# Motherboard_v2.net
KiCad netlist of a schematic drawn in EAGLE
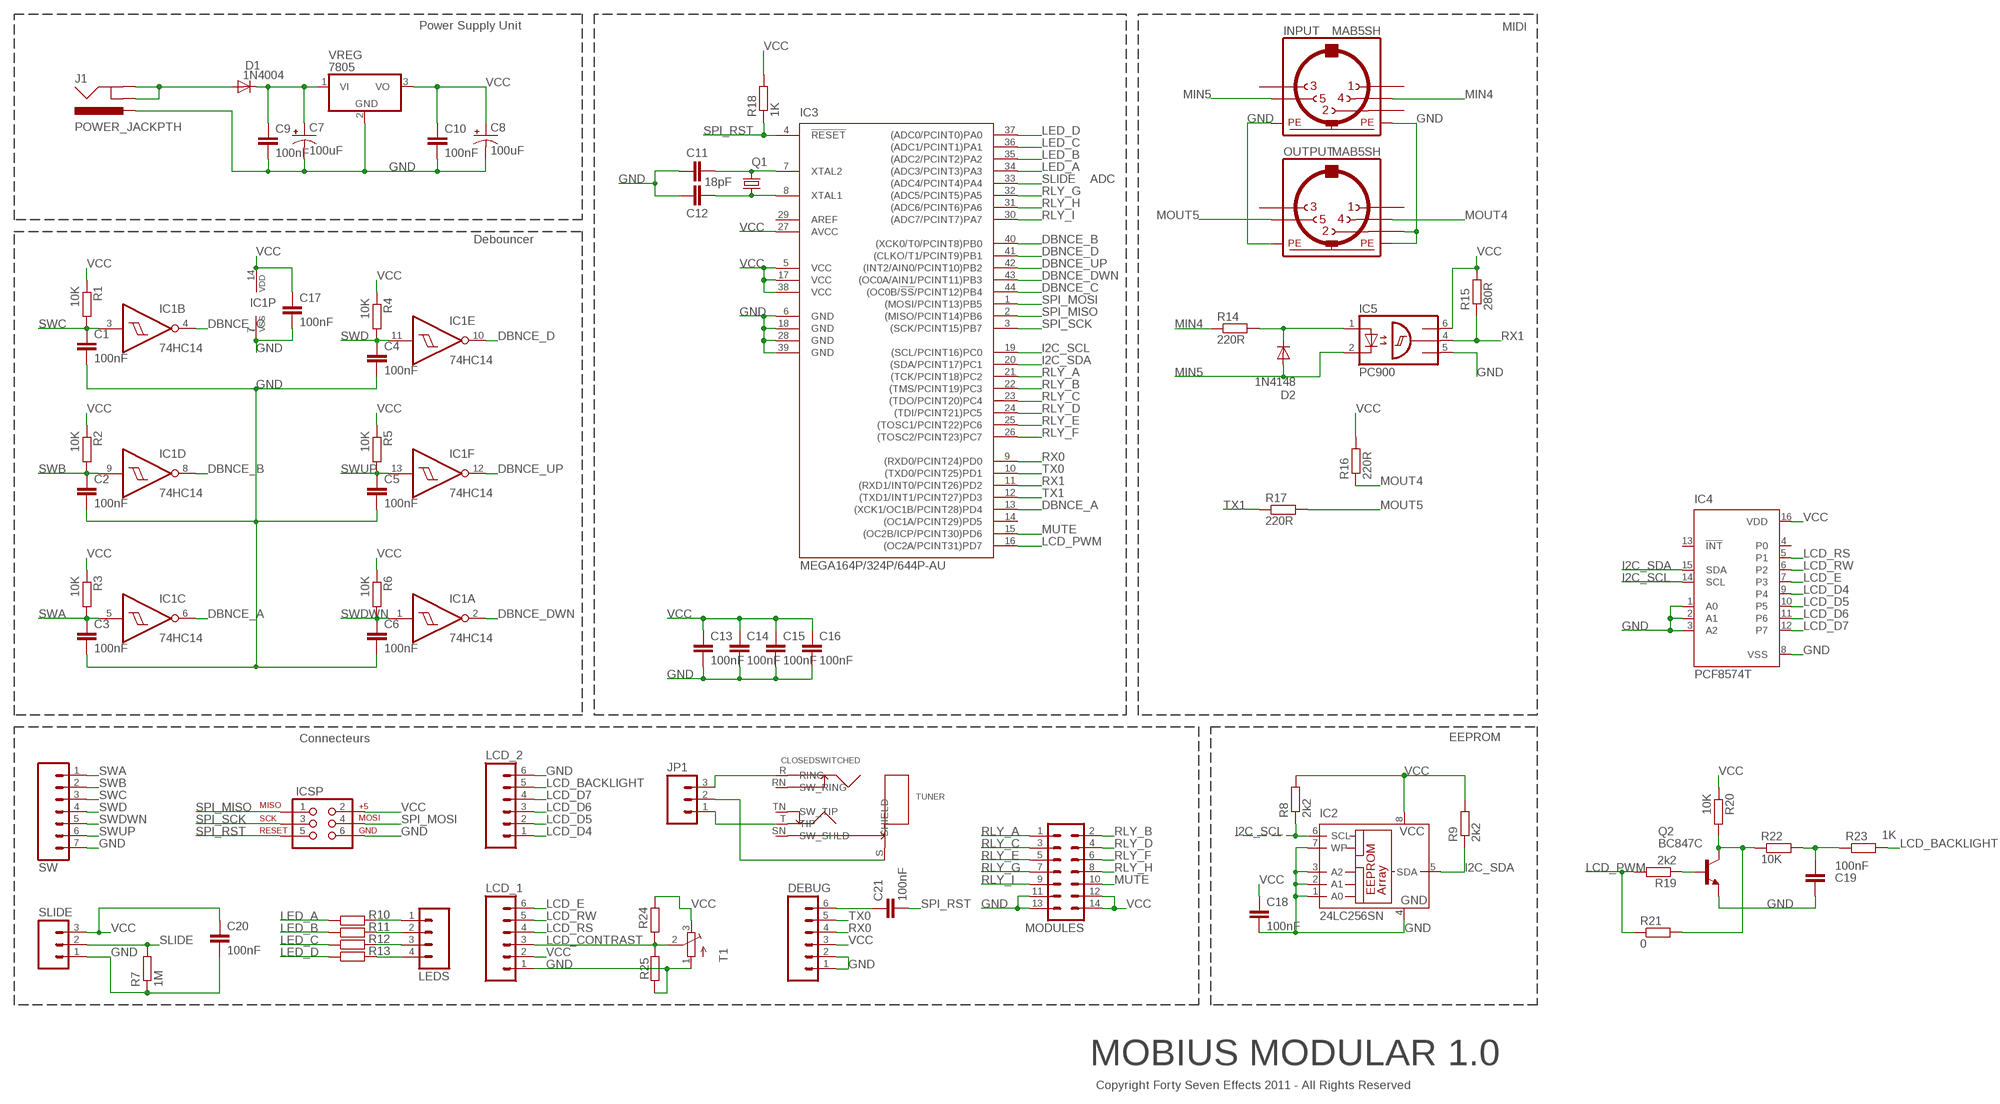
[diagram p0: schematic, sheet 1]

(export (version "E")
  (design (tool "Eeschema 10.0.6"))
  (components
    (comp (ref "C1")
      (value "100nF")
      (footprint "eagle-import:C0805K")
      (libsource (lib "eagle-import") (part "C-EUC0805K"))
    )
    (comp (ref "C2")
      (value "100nF")
      (footprint "eagle-import:C0805K")
      (libsource (lib "eagle-import") (part "C-EUC0805K"))
    )
    (comp (ref "C3")
      (value "100nF")
      (footprint "eagle-import:C0805K")
      (libsource (lib "eagle-import") (part "C-EUC0805K"))
    )
    (comp (ref "C4")
      (value "100nF")
      (footprint "eagle-import:C0805K")
      (libsource (lib "eagle-import") (part "C-EUC0805K"))
    )
    (comp (ref "C5")
      (value "100nF")
      (footprint "eagle-import:C0805K")
      (libsource (lib "eagle-import") (part "C-EUC0805K"))
    )
    (comp (ref "C6")
      (value "100nF")
      (footprint "eagle-import:C0805K")
      (libsource (lib "eagle-import") (part "C-EUC0805K"))
    )
    (comp (ref "C7")
      (value "100uF")
      (footprint "eagle-import:E2,5-6E")
      (libsource (lib "eagle-import") (part "CPOL-USE2,5-6E"))
    )
    (comp (ref "C8")
      (value "100uF")
      (footprint "eagle-import:E2,5-6E")
      (libsource (lib "eagle-import") (part "CPOL-USE2,5-6E"))
    )
    (comp (ref "C9")
      (value "100nF")
      (footprint "eagle-import:C0805K")
      (libsource (lib "eagle-import") (part "C-EUC0805K"))
    )
    (comp (ref "C10")
      (value "100nF")
      (footprint "eagle-import:C0805K")
      (libsource (lib "eagle-import") (part "C-EUC0805K"))
    )
    (comp (ref "C11")
      (value "18pF")
      (footprint "eagle-import:C0805K")
      (libsource (lib "eagle-import") (part "C-EUC0805K"))
    )
    (comp (ref "C12")
      (value "18pF")
      (footprint "eagle-import:C0805K")
      (libsource (lib "eagle-import") (part "C-EUC0805K"))
    )
    (comp (ref "C13")
      (value "100nF")
      (footprint "eagle-import:C0805K")
      (libsource (lib "eagle-import") (part "C-EUC0805K"))
    )
    (comp (ref "C14")
      (value "100nF")
      (footprint "eagle-import:C0805K")
      (libsource (lib "eagle-import") (part "C-EUC0805K"))
    )
    (comp (ref "C15")
      (value "100nF")
      (footprint "eagle-import:C0805K")
      (libsource (lib "eagle-import") (part "C-EUC0805K"))
    )
    (comp (ref "C16")
      (value "100nF")
      (footprint "eagle-import:C0805K")
      (libsource (lib "eagle-import") (part "C-EUC0805K"))
    )
    (comp (ref "C17")
      (value "100nF")
      (footprint "eagle-import:C0805K")
      (libsource (lib "eagle-import") (part "C-EUC0805K"))
    )
    (comp (ref "C18")
      (value "100nF")
      (footprint "eagle-import:C0805K")
      (libsource (lib "eagle-import") (part "C-EUC0805K"))
    )
    (comp (ref "C19")
      (value "100nF")
      (footprint "eagle-import:C0805K")
      (libsource (lib "eagle-import") (part "C-EUC0805K"))
    )
    (comp (ref "C20")
      (value "100nF")
      (footprint "eagle-import:C0805K")
      (libsource (lib "eagle-import") (part "C-EUC0805K"))
    )
    (comp (ref "C21")
      (value "100nF")
      (footprint "eagle-import:C0805K")
      (libsource (lib "eagle-import") (part "C-EUC0805K"))
    )
    (comp (ref "D1")
      (value "1N4004")
      (footprint "eagle-import:DO41-10")
      (libsource (lib "eagle-import") (part "1N4004"))
    )
    (comp (ref "D2")
      (value "1N4148")
      (footprint "eagle-import:DO35-7")
      (libsource (lib "eagle-import") (part "1N4148DO35-7"))
    )
    (comp (ref "DEBUG")
      (value "M06SIP")
      (footprint "eagle-import:1X06")
      (libsource (lib "eagle-import") (part "M06SIP"))
    )
    (comp (ref "IC1")
      (value "74HC14")
      (footprint "eagle-import:SO14")
      (libsource (lib "eagle-import") (part "40106D"))
    )
    (comp (ref "IC2")
      (value "24LC256SN")
      (footprint "eagle-import:SO-08")
      (libsource (lib "eagle-import") (part "24SNLC256"))
    )
    (comp (ref "IC3")
      (value "MEGA164P/324P/644P-AU")
      (footprint "eagle-import:TQFP44")
      (libsource (lib "eagle-import") (part "MEGA164P/324P/644P-AU"))
    )
    (comp (ref "IC4")
      (value "PCF8574T")
      (footprint "eagle-import:SO16W")
      (fields (field (name "MPN") "PCF8574T/3,512"))
      (libsource (lib "eagle-import") (part "PCF8574T"))
    )
    (comp (ref "IC5")
      (value "PC900")
      (footprint "eagle-import:DIL06")
      (libsource (lib "eagle-import") (part "OPI8013"))
    )
    (comp (ref "ICSP")
      (value "AVR_SPI_PRG_6PTH")
      (footprint "eagle-import:2X3")
      (libsource (lib "eagle-import") (part "AVR_SPI_PRG_6PTH"))
    )
    (comp (ref "INPUT")
      (value "MAB5SH")
      (footprint "eagle-import:MAB5SH")
      (libsource (lib "eagle-import") (part "MAB5SH"))
    )
    (comp (ref "J1")
      (value "POWER_JACKPTH")
      (footprint "eagle-import:POWER_JACK_PTH")
      (libsource (lib "eagle-import") (part "POWER_JACKPTH"))
    )
    (comp (ref "JP1")
      (value "M03POLAR")
      (footprint "eagle-import:MOLEX-1X3")
      (libsource (lib "eagle-import") (part "M03POLAR"))
    )
    (comp (ref "LCD_1")
      (value "M06SIP")
      (footprint "eagle-import:1X06")
      (libsource (lib "eagle-import") (part "M06SIP"))
    )
    (comp (ref "LCD_2")
      (value "M06SIP")
      (footprint "eagle-import:1X06")
      (libsource (lib "eagle-import") (part "M06SIP"))
    )
    (comp (ref "LEDS")
      (value "M04PTH")
      (footprint "eagle-import:1X04")
      (libsource (lib "eagle-import") (part "M04PTH"))
    )
    (comp (ref "MODULES")
      (value "ML14")
      (footprint "eagle-import:ML14")
      (libsource (lib "eagle-import") (part "ML14"))
    )
    (comp (ref "OUTPUT")
      (value "MAB5SH")
      (footprint "eagle-import:MAB5SH")
      (libsource (lib "eagle-import") (part "MAB5SH"))
    )
    (comp (ref "Q1")
      (value "16MHz")
      (footprint "eagle-import:CRYSTAL-SMD-5X3")
      (libsource (lib "eagle-import") (part "CRYSTAL5X3"))
    )
    (comp (ref "Q2")
      (value "BC847C")
      (footprint "eagle-import:SOT23")
      (libsource (lib "eagle-import") (part "BC847SMDC"))
    )
    (comp (ref "R1")
      (value "10K")
      (footprint "eagle-import:M0805")
      (libsource (lib "eagle-import") (part "R-EU_M0805"))
    )
    (comp (ref "R2")
      (value "10K")
      (footprint "eagle-import:M0805")
      (libsource (lib "eagle-import") (part "R-EU_M0805"))
    )
    (comp (ref "R3")
      (value "10K")
      (footprint "eagle-import:M0805")
      (libsource (lib "eagle-import") (part "R-EU_M0805"))
    )
    (comp (ref "R4")
      (value "10K")
      (footprint "eagle-import:M0805")
      (libsource (lib "eagle-import") (part "R-EU_M0805"))
    )
    (comp (ref "R5")
      (value "10K")
      (footprint "eagle-import:M0805")
      (libsource (lib "eagle-import") (part "R-EU_M0805"))
    )
    (comp (ref "R6")
      (value "10K")
      (footprint "eagle-import:M0805")
      (libsource (lib "eagle-import") (part "R-EU_M0805"))
    )
    (comp (ref "R7")
      (value "1M")
      (footprint "eagle-import:M0805")
      (libsource (lib "eagle-import") (part "R-EU_M0805"))
    )
    (comp (ref "R8")
      (value "2k2")
      (footprint "eagle-import:M0805")
      (libsource (lib "eagle-import") (part "R-EU_M0805"))
    )
    (comp (ref "R9")
      (value "2k2")
      (footprint "eagle-import:M0805")
      (libsource (lib "eagle-import") (part "R-EU_M0805"))
    )
    (comp (ref "R10")
      (value "1k")
      (footprint "eagle-import:M0805")
      (libsource (lib "eagle-import") (part "R-EU_M0805"))
    )
    (comp (ref "R11")
      (value "1K")
      (footprint "eagle-import:M0805")
      (libsource (lib "eagle-import") (part "R-EU_M0805"))
    )
    (comp (ref "R12")
      (value "1k")
      (footprint "eagle-import:M0805")
      (libsource (lib "eagle-import") (part "R-EU_M0805"))
    )
    (comp (ref "R13")
      (value "1k")
      (footprint "eagle-import:M0805")
      (libsource (lib "eagle-import") (part "R-EU_M0805"))
    )
    (comp (ref "R14")
      (value "220R")
      (footprint "eagle-import:M0805")
      (libsource (lib "eagle-import") (part "R-EU_M0805"))
    )
    (comp (ref "R15")
      (value "280R")
      (footprint "eagle-import:M0805")
      (libsource (lib "eagle-import") (part "R-EU_M0805"))
    )
    (comp (ref "R16")
      (value "220R")
      (footprint "eagle-import:M0805")
      (libsource (lib "eagle-import") (part "R-EU_M0805"))
    )
    (comp (ref "R17")
      (value "220R")
      (footprint "eagle-import:M0805")
      (libsource (lib "eagle-import") (part "R-EU_M0805"))
    )
    (comp (ref "R18")
      (value "1K")
      (footprint "eagle-import:M0805")
      (libsource (lib "eagle-import") (part "R-EU_M0805"))
    )
    (comp (ref "R19")
      (value "2k2")
      (footprint "eagle-import:M0805")
      (libsource (lib "eagle-import") (part "R-EU_M0805"))
    )
    (comp (ref "R20")
      (value "10K")
      (footprint "eagle-import:M0805")
      (libsource (lib "eagle-import") (part "R-EU_M0805"))
    )
    (comp (ref "R21")
      (value "0")
      (footprint "eagle-import:M0805")
      (libsource (lib "eagle-import") (part "R-EU_M0805"))
    )
    (comp (ref "R22")
      (value "10K")
      (footprint "eagle-import:M0805")
      (libsource (lib "eagle-import") (part "R-EU_M0805"))
    )
    (comp (ref "R23")
      (value "1K")
      (footprint "eagle-import:M0805")
      (libsource (lib "eagle-import") (part "R-EU_M0805"))
    )
    (comp (ref "R24")
      (value "1k")
      (footprint "eagle-import:M0805")
      (libsource (lib "eagle-import") (part "R-EU_M0805"))
    )
    (comp (ref "R25")
      (value "1k")
      (footprint "eagle-import:M0805")
      (libsource (lib "eagle-import") (part "R-EU_M0805"))
    )
    (comp (ref "SLIDE")
      (value "M03PTH")
      (footprint "eagle-import:1X03")
      (libsource (lib "eagle-import") (part "M03PTH"))
    )
    (comp (ref "SW")
      (value "M07")
      (footprint "eagle-import:1X07")
      (libsource (lib "eagle-import") (part "M07"))
    )
    (comp (ref "T1")
      (value "TRIMPOTTC33X")
      (footprint "eagle-import:TC33X")
      (libsource (lib "eagle-import") (part "TRIMPOTTC33X"))
    )
    (comp (ref "TUNER")
      (value "CLOSEDSWITCHED")
      (footprint "eagle-import:NMJ6HFD2")
      (libsource (lib "eagle-import") (part "CLOSEDSWITCHED"))
    )
    (comp (ref "VREG")
      (value "7805")
      (footprint "eagle-import:TO220V")
      (libsource (lib "eagle-import") (part "78TV05"))
    )
  )
  (nets
    (net (code "1") (name "/AREF") (class "Default")
      (node (ref "IC3") (pin "29") (pinfunction "AREF_29") (pintype "power_in"))
    )
    (net (code "2") (name "/DBNCE_A") (class "Default")
      (node (ref "IC1") (pin "6") (pinfunction "O_6") (pintype "output"))
      (node (ref "IC3") (pin "13") (pinfunction "(XCK1/OC1B/PCINT28)PD4_13") (pintype "bidirectional"))
    )
    (net (code "3") (name "/DBNCE_B") (class "Default")
      (node (ref "IC1") (pin "8") (pinfunction "O_8") (pintype "output"))
      (node (ref "IC3") (pin "40") (pinfunction "(XCK0/T0/PCINT8)PB0_40") (pintype "bidirectional"))
    )
    (net (code "4") (name "/DBNCE_C") (class "Default")
      (node (ref "IC1") (pin "4") (pinfunction "O_4") (pintype "output"))
      (node (ref "IC3") (pin "44") (pinfunction "(OC0B/~{SS}/PCINT12)PB4_44") (pintype "bidirectional"))
    )
    (net (code "5") (name "/DBNCE_D") (class "Default")
      (node (ref "IC1") (pin "10") (pinfunction "O_10") (pintype "output"))
      (node (ref "IC3") (pin "41") (pinfunction "(CLKO/T1/PCINT9)PB1_41") (pintype "bidirectional"))
    )
    (net (code "6") (name "/DBNCE_DWN") (class "Default")
      (node (ref "IC1") (pin "2") (pinfunction "O_2") (pintype "output"))
      (node (ref "IC3") (pin "43") (pinfunction "(OC0A/AIN1/PCINT11)PB3_43") (pintype "bidirectional"))
    )
    (net (code "7") (name "/DBNCE_UP") (class "Default")
      (node (ref "IC1") (pin "12") (pinfunction "O_12") (pintype "output"))
      (node (ref "IC3") (pin "42") (pinfunction "(INT2/AIN0/PCINT10)PB2_42") (pintype "bidirectional"))
    )
    (net (code "8") (name "/GND") (class "Default")
      (node (ref "C1") (pin "2") (pinfunction "2_2") (pintype "passive"))
      (node (ref "C10") (pin "2") (pinfunction "2_2") (pintype "passive"))
      (node (ref "C11") (pin "1") (pinfunction "1_1") (pintype "passive"))
      (node (ref "C12") (pin "1") (pinfunction "1_1") (pintype "passive"))
      (node (ref "C13") (pin "2") (pinfunction "2_2") (pintype "passive"))
      (node (ref "C14") (pin "2") (pinfunction "2_2") (pintype "passive"))
      (node (ref "C15") (pin "2") (pinfunction "2_2") (pintype "passive"))
      (node (ref "C16") (pin "2") (pinfunction "2_2") (pintype "passive"))
      (node (ref "C17") (pin "2") (pinfunction "2_2") (pintype "passive"))
      (node (ref "C18") (pin "2") (pinfunction "2_2") (pintype "passive"))
      (node (ref "C19") (pin "1") (pinfunction "1_1") (pintype "passive"))
      (node (ref "C2") (pin "2") (pinfunction "2_2") (pintype "passive"))
      (node (ref "C20") (pin "2") (pinfunction "2_2") (pintype "passive"))
      (node (ref "C3") (pin "2") (pinfunction "2_2") (pintype "passive"))
      (node (ref "C4") (pin "2") (pinfunction "2_2") (pintype "passive"))
      (node (ref "C5") (pin "2") (pinfunction "2_2") (pintype "passive"))
      (node (ref "C6") (pin "2") (pinfunction "2_2") (pintype "passive"))
      (node (ref "C7") (pin "-") (pinfunction "-_-") (pintype "passive"))
      (node (ref "C8") (pin "-") (pinfunction "-_-") (pintype "passive"))
      (node (ref "C9") (pin "2") (pinfunction "2_2") (pintype "passive"))
      (node (ref "DEBUG") (pin "1") (pinfunction "1_1") (pintype "passive"))
      (node (ref "DEBUG") (pin "2") (pinfunction "2_2") (pintype "passive"))
      (node (ref "IC1") (pin "7") (pinfunction "VSS_7") (pintype "power_in"))
      (node (ref "IC2") (pin "1") (pinfunction "A0_1") (pintype "input"))
      (node (ref "IC2") (pin "2") (pinfunction "A1_2") (pintype "input"))
      (node (ref "IC2") (pin "3") (pinfunction "A2_3") (pintype "input"))
      (node (ref "IC2") (pin "4") (pinfunction "GND_4") (pintype "power_in"))
      (node (ref "IC2") (pin "7") (pinfunction "WP_7") (pintype "input"))
      (node (ref "IC3") (pin "18") (pinfunction "GND_18") (pintype "power_in"))
      (node (ref "IC3") (pin "28") (pinfunction "GND_28") (pintype "power_in"))
      (node (ref "IC3") (pin "39") (pinfunction "GND_39") (pintype "power_in"))
      (node (ref "IC3") (pin "6") (pinfunction "GND_6") (pintype "power_in"))
      (node (ref "IC4") (pin "1") (pinfunction "A0_1") (pintype "input"))
      (node (ref "IC4") (pin "2") (pinfunction "A1_2") (pintype "input"))
      (node (ref "IC4") (pin "3") (pinfunction "A2_3") (pintype "input"))
      (node (ref "IC4") (pin "8") (pinfunction "VSS_8") (pintype "power_in"))
      (node (ref "IC5") (pin "5") (pinfunction "GND_5") (pintype "passive"))
      (node (ref "ICSP") (pin "6") (pinfunction "6_6") (pintype "passive"))
      (node (ref "INPUT") (pin "PE") (pinfunction "PE_PE") (pintype "power_in"))
      (node (ref "INPUT") (pin "PE@") (pinfunction "PE_PE@") (pintype "power_in"))
      (node (ref "J1") (pin "PWR") (pinfunction "PWR_PWR") (pintype "bidirectional"))
      (node (ref "LCD_1") (pin "1") (pinfunction "1_1") (pintype "passive"))
      (node (ref "LCD_2") (pin "6") (pinfunction "6_6") (pintype "passive"))
      (node (ref "MODULES") (pin "11") (pinfunction "11_11") (pintype "passive"))
      (node (ref "MODULES") (pin "13") (pinfunction "13_13") (pintype "passive"))
      (node (ref "OUTPUT") (pin "2") (pinfunction "2_2") (pintype "passive"))
      (node (ref "OUTPUT") (pin "PE") (pinfunction "PE_PE") (pintype "power_in"))
      (node (ref "OUTPUT") (pin "PE@") (pinfunction "PE_PE@") (pintype "power_in"))
      (node (ref "Q2") (pin "2") (pinfunction "E_2") (pintype "passive"))
      (node (ref "R25") (pin "1") (pinfunction "1_1") (pintype "passive"))
      (node (ref "R7") (pin "1") (pinfunction "1_1") (pintype "passive"))
      (node (ref "SLIDE") (pin "1") (pinfunction "1_1") (pintype "passive"))
      (node (ref "SW") (pin "7") (pinfunction "7_7") (pintype "passive"))
      (node (ref "T1") (pin "1") (pinfunction "A_1") (pintype "passive"))
      (node (ref "VREG") (pin "2") (pinfunction "GND_2") (pintype "passive"))
    )
    (net (code "9") (name "/I2C_SCL") (class "Default")
      (node (ref "IC2") (pin "6") (pinfunction "SCL_6") (pintype "input"))
      (node (ref "IC3") (pin "19") (pinfunction "(SCL/PCINT16)PC0_19") (pintype "bidirectional"))
      (node (ref "IC4") (pin "14") (pinfunction "SCL_14") (pintype "input"))
      (node (ref "R8") (pin "1") (pinfunction "1_1") (pintype "passive"))
    )
    (net (code "10") (name "/I2C_SDA") (class "Default")
      (node (ref "IC2") (pin "5") (pinfunction "SDA_5") (pintype "bidirectional"))
      (node (ref "IC3") (pin "20") (pinfunction "(SDA/PCINT17)PC1_20") (pintype "bidirectional"))
      (node (ref "IC4") (pin "15") (pinfunction "SDA_15") (pintype "bidirectional"))
      (node (ref "R9") (pin "1") (pinfunction "1_1") (pintype "passive"))
    )
    (net (code "11") (name "/LCD_BACKLIGHT") (class "Default")
      (node (ref "LCD_2") (pin "5") (pinfunction "5_5") (pintype "passive"))
      (node (ref "R23") (pin "2") (pinfunction "2_2") (pintype "passive"))
    )
    (net (code "12") (name "/LCD_CONTRAST") (class "Default")
      (node (ref "LCD_1") (pin "3") (pinfunction "3_3") (pintype "passive"))
      (node (ref "R24") (pin "1") (pinfunction "1_1") (pintype "passive"))
      (node (ref "R25") (pin "2") (pinfunction "2_2") (pintype "passive"))
      (node (ref "T1") (pin "2") (pinfunction "S_2") (pintype "passive"))
    )
    (net (code "13") (name "/LCD_D4") (class "Default")
      (node (ref "IC4") (pin "9") (pinfunction "P4_9") (pintype "bidirectional"))
      (node (ref "LCD_2") (pin "1") (pinfunction "1_1") (pintype "passive"))
    )
    (net (code "14") (name "/LCD_D5") (class "Default")
      (node (ref "IC4") (pin "10") (pinfunction "P5_10") (pintype "bidirectional"))
      (node (ref "LCD_2") (pin "2") (pinfunction "2_2") (pintype "passive"))
    )
    (net (code "15") (name "/LCD_D6") (class "Default")
      (node (ref "IC4") (pin "11") (pinfunction "P6_11") (pintype "bidirectional"))
      (node (ref "LCD_2") (pin "3") (pinfunction "3_3") (pintype "passive"))
    )
    (net (code "16") (name "/LCD_D7") (class "Default")
      (node (ref "IC4") (pin "12") (pinfunction "P7_12") (pintype "bidirectional"))
      (node (ref "LCD_2") (pin "4") (pinfunction "4_4") (pintype "passive"))
    )
    (net (code "17") (name "/LCD_E") (class "Default")
      (node (ref "IC4") (pin "7") (pinfunction "P3_7") (pintype "bidirectional"))
      (node (ref "LCD_1") (pin "6") (pinfunction "6_6") (pintype "passive"))
    )
    (net (code "18") (name "/LCD_PWM") (class "Default")
      (node (ref "IC3") (pin "16") (pinfunction "(OC2A/PCINT31)PD7_16") (pintype "bidirectional"))
      (node (ref "R19") (pin "2") (pinfunction "2_2") (pintype "passive"))
      (node (ref "R21") (pin "1") (pinfunction "1_1") (pintype "passive"))
    )
    (net (code "19") (name "/LCD_RS") (class "Default")
      (node (ref "IC4") (pin "5") (pinfunction "P1_5") (pintype "bidirectional"))
      (node (ref "LCD_1") (pin "4") (pinfunction "4_4") (pintype "passive"))
    )
    (net (code "20") (name "/LCD_RW") (class "Default")
      (node (ref "IC4") (pin "6") (pinfunction "P2_6") (pintype "bidirectional"))
      (node (ref "LCD_1") (pin "5") (pinfunction "5_5") (pintype "passive"))
    )
    (net (code "21") (name "/LED_A") (class "Default")
      (node (ref "IC3") (pin "34") (pinfunction "(ADC3/PCINT3)PA3_34") (pintype "bidirectional"))
      (node (ref "R10") (pin "1") (pinfunction "1_1") (pintype "passive"))
    )
    (net (code "22") (name "/LED_B") (class "Default")
      (node (ref "IC3") (pin "35") (pinfunction "(ADC2/PCINT2)PA2_35") (pintype "bidirectional"))
      (node (ref "R11") (pin "1") (pinfunction "1_1") (pintype "passive"))
    )
    (net (code "23") (name "/LED_C") (class "Default")
      (node (ref "IC3") (pin "36") (pinfunction "(ADC1/PCINT1)PA1_36") (pintype "bidirectional"))
      (node (ref "R12") (pin "1") (pinfunction "1_1") (pintype "passive"))
    )
    (net (code "24") (name "/LED_D") (class "Default")
      (node (ref "IC3") (pin "37") (pinfunction "(ADC0/PCINT0)PA0_37") (pintype "bidirectional"))
      (node (ref "R13") (pin "1") (pinfunction "1_1") (pintype "passive"))
    )
    (net (code "25") (name "/MIN4") (class "Default")
      (node (ref "INPUT") (pin "4") (pinfunction "4_4") (pintype "passive"))
      (node (ref "R14") (pin "1") (pinfunction "1_1") (pintype "passive"))
    )
    (net (code "26") (name "/MIN5") (class "Default")
      (node (ref "D2") (pin "A") (pinfunction "A_A") (pintype "passive"))
      (node (ref "IC5") (pin "2") (pinfunction "C_2") (pintype "passive"))
      (node (ref "INPUT") (pin "5") (pinfunction "5_5") (pintype "passive"))
    )
    (net (code "27") (name "/MOUT4") (class "Default")
      (node (ref "OUTPUT") (pin "4") (pinfunction "4_4") (pintype "passive"))
      (node (ref "R16") (pin "1") (pinfunction "1_1") (pintype "passive"))
    )
    (net (code "28") (name "/MOUT5") (class "Default")
      (node (ref "OUTPUT") (pin "5") (pinfunction "5_5") (pintype "passive"))
      (node (ref "R17") (pin "2") (pinfunction "2_2") (pintype "passive"))
    )
    (net (code "29") (name "/MUTE") (class "Default")
      (node (ref "IC3") (pin "15") (pinfunction "(OC2B/ICP/PCINT30)PD6_15") (pintype "bidirectional"))
      (node (ref "MODULES") (pin "10") (pinfunction "10_10") (pintype "passive"))
    )
    (net (code "30") (name "/RLY_A") (class "Default")
      (node (ref "IC3") (pin "21") (pinfunction "(TCK/PCINT18)PC2_21") (pintype "bidirectional"))
      (node (ref "MODULES") (pin "1") (pinfunction "1_1") (pintype "passive"))
    )
    (net (code "31") (name "/RLY_B") (class "Default")
      (node (ref "IC3") (pin "22") (pinfunction "(TMS/PCINT19)PC3_22") (pintype "bidirectional"))
      (node (ref "MODULES") (pin "2") (pinfunction "2_2") (pintype "passive"))
    )
    (net (code "32") (name "/RLY_C") (class "Default")
      (node (ref "IC3") (pin "23") (pinfunction "(TDO/PCINT20)PC4_23") (pintype "bidirectional"))
      (node (ref "MODULES") (pin "3") (pinfunction "3_3") (pintype "passive"))
    )
    (net (code "33") (name "/RLY_D") (class "Default")
      (node (ref "IC3") (pin "24") (pinfunction "(TDI/PCINT21)PC5_24") (pintype "bidirectional"))
      (node (ref "MODULES") (pin "4") (pinfunction "4_4") (pintype "passive"))
    )
    (net (code "34") (name "/RLY_E") (class "Default")
      (node (ref "IC3") (pin "25") (pinfunction "(TOSC1/PCINT22)PC6_25") (pintype "bidirectional"))
      (node (ref "MODULES") (pin "5") (pinfunction "5_5") (pintype "passive"))
    )
    (net (code "35") (name "/RLY_F") (class "Default")
      (node (ref "IC3") (pin "26") (pinfunction "(TOSC2/PCINT23)PC7_26") (pintype "bidirectional"))
      (node (ref "MODULES") (pin "6") (pinfunction "6_6") (pintype "passive"))
    )
    (net (code "36") (name "/RLY_G") (class "Default")
      (node (ref "IC3") (pin "32") (pinfunction "(ADC5/PCINT5)PA5_32") (pintype "bidirectional"))
      (node (ref "MODULES") (pin "7") (pinfunction "7_7") (pintype "passive"))
    )
    (net (code "37") (name "/RLY_H") (class "Default")
      (node (ref "IC3") (pin "31") (pinfunction "(ADC6/PCINT6)PA6_31") (pintype "bidirectional"))
      (node (ref "MODULES") (pin "8") (pinfunction "8_8") (pintype "passive"))
    )
    (net (code "38") (name "/RLY_I") (class "Default")
      (node (ref "IC3") (pin "30") (pinfunction "(ADC7/PCINT7)PA7_30") (pintype "bidirectional"))
      (node (ref "MODULES") (pin "9") (pinfunction "9_9") (pintype "passive"))
    )
    (net (code "39") (name "/RX0") (class "Default")
      (node (ref "DEBUG") (pin "4") (pinfunction "4_4") (pintype "passive"))
      (node (ref "IC3") (pin "9") (pinfunction "(RXD0/PCINT24)PD0_9") (pintype "bidirectional"))
    )
    (net (code "40") (name "/RX1") (class "Default")
      (node (ref "IC3") (pin "11") (pinfunction "(RXD1/INT0/PCINT26)PD2_11") (pintype "bidirectional"))
      (node (ref "IC5") (pin "4") (pinfunction "OUT_4") (pintype "passive"))
      (node (ref "R15") (pin "1") (pinfunction "1_1") (pintype "passive"))
    )
    (net (code "41") (name "/SLIDE") (class "Default")
      (node (ref "IC3") (pin "33") (pinfunction "(ADC4/PCINT4)PA4_33") (pintype "bidirectional"))
      (node (ref "R7") (pin "2") (pinfunction "2_2") (pintype "passive"))
      (node (ref "SLIDE") (pin "2") (pinfunction "2_2") (pintype "passive"))
    )
    (net (code "42") (name "/SPI_MISO") (class "Default")
      (node (ref "IC3") (pin "2") (pinfunction "(MISO/PCINT14)PB6_2") (pintype "bidirectional"))
      (node (ref "ICSP") (pin "1") (pinfunction "1_1") (pintype "passive"))
    )
    (net (code "43") (name "/SPI_MOSI") (class "Default")
      (node (ref "IC3") (pin "1") (pinfunction "(MOSI/PCINT13)PB5_1") (pintype "bidirectional"))
      (node (ref "ICSP") (pin "4") (pinfunction "4_4") (pintype "passive"))
    )
    (net (code "44") (name "/SPI_RST") (class "Default")
      (node (ref "C21") (pin "2") (pinfunction "2_2") (pintype "passive"))
      (node (ref "IC3") (pin "4") (pinfunction "~{RESET}_4") (pintype "input"))
      (node (ref "ICSP") (pin "5") (pinfunction "5_5") (pintype "passive"))
      (node (ref "R18") (pin "1") (pinfunction "1_1") (pintype "passive"))
    )
    (net (code "45") (name "/SPI_SCK") (class "Default")
      (node (ref "IC3") (pin "3") (pinfunction "(SCK/PCINT15)PB7_3") (pintype "bidirectional"))
      (node (ref "ICSP") (pin "3") (pinfunction "3_3") (pintype "passive"))
    )
    (net (code "46") (name "/SWA") (class "Default")
      (node (ref "C3") (pin "1") (pinfunction "1_1") (pintype "passive"))
      (node (ref "IC1") (pin "5") (pinfunction "I_5") (pintype "input"))
      (node (ref "R3") (pin "2") (pinfunction "2_2") (pintype "passive"))
      (node (ref "SW") (pin "1") (pinfunction "1_1") (pintype "passive"))
    )
    (net (code "47") (name "/SWB") (class "Default")
      (node (ref "C2") (pin "1") (pinfunction "1_1") (pintype "passive"))
      (node (ref "IC1") (pin "9") (pinfunction "I_9") (pintype "input"))
      (node (ref "R2") (pin "2") (pinfunction "2_2") (pintype "passive"))
      (node (ref "SW") (pin "2") (pinfunction "2_2") (pintype "passive"))
    )
    (net (code "48") (name "/SWC") (class "Default")
      (node (ref "C1") (pin "1") (pinfunction "1_1") (pintype "passive"))
      (node (ref "IC1") (pin "3") (pinfunction "I_3") (pintype "input"))
      (node (ref "R1") (pin "2") (pinfunction "2_2") (pintype "passive"))
      (node (ref "SW") (pin "3") (pinfunction "3_3") (pintype "passive"))
    )
    (net (code "49") (name "/SWD") (class "Default")
      (node (ref "C4") (pin "1") (pinfunction "1_1") (pintype "passive"))
      (node (ref "IC1") (pin "11") (pinfunction "I_11") (pintype "input"))
      (node (ref "R4") (pin "2") (pinfunction "2_2") (pintype "passive"))
      (node (ref "SW") (pin "4") (pinfunction "4_4") (pintype "passive"))
    )
    (net (code "50") (name "/SWDWN") (class "Default")
      (node (ref "C6") (pin "1") (pinfunction "1_1") (pintype "passive"))
      (node (ref "IC1") (pin "1") (pinfunction "I_1") (pintype "input"))
      (node (ref "R6") (pin "2") (pinfunction "2_2") (pintype "passive"))
      (node (ref "SW") (pin "5") (pinfunction "5_5") (pintype "passive"))
    )
    (net (code "51") (name "/SWUP") (class "Default")
      (node (ref "C5") (pin "1") (pinfunction "1_1") (pintype "passive"))
      (node (ref "IC1") (pin "13") (pinfunction "I_13") (pintype "input"))
      (node (ref "R5") (pin "2") (pinfunction "2_2") (pintype "passive"))
      (node (ref "SW") (pin "6") (pinfunction "6_6") (pintype "passive"))
    )
    (net (code "52") (name "/TX0") (class "Default")
      (node (ref "DEBUG") (pin "5") (pinfunction "5_5") (pintype "passive"))
      (node (ref "IC3") (pin "10") (pinfunction "(TXD0/PCINT25)PD1_10") (pintype "bidirectional"))
    )
    (net (code "53") (name "/TX1") (class "Default")
      (node (ref "IC3") (pin "12") (pinfunction "(TXD1/INT1/PCINT27)PD3_12") (pintype "bidirectional"))
      (node (ref "R17") (pin "1") (pinfunction "1_1") (pintype "passive"))
    )
    (net (code "54") (name "/VCC") (class "Default")
      (node (ref "C10") (pin "1") (pinfunction "1_1") (pintype "passive"))
      (node (ref "C13") (pin "1") (pinfunction "1_1") (pintype "passive"))
      (node (ref "C14") (pin "1") (pinfunction "1_1") (pintype "passive"))
      (node (ref "C15") (pin "1") (pinfunction "1_1") (pintype "passive"))
      (node (ref "C16") (pin "1") (pinfunction "1_1") (pintype "passive"))
      (node (ref "C17") (pin "1") (pinfunction "1_1") (pintype "passive"))
      (node (ref "C18") (pin "1") (pinfunction "1_1") (pintype "passive"))
      (node (ref "C20") (pin "1") (pinfunction "1_1") (pintype "passive"))
      (node (ref "C8") (pin "+") (pinfunction "+_+") (pintype "passive"))
      (node (ref "DEBUG") (pin "3") (pinfunction "3_3") (pintype "passive"))
      (node (ref "IC1") (pin "14") (pinfunction "VDD_14") (pintype "power_in"))
      (node (ref "IC2") (pin "8") (pinfunction "VCC_8") (pintype "power_in"))
      (node (ref "IC3") (pin "17") (pinfunction "VCC_17") (pintype "power_in"))
      (node (ref "IC3") (pin "27") (pinfunction "AVCC_27") (pintype "power_in"))
      (node (ref "IC3") (pin "38") (pinfunction "VCC_38") (pintype "power_in"))
      (node (ref "IC3") (pin "5") (pinfunction "VCC_5") (pintype "power_in"))
      (node (ref "IC4") (pin "16") (pinfunction "VDD_16") (pintype "power_in"))
      (node (ref "IC5") (pin "6") (pinfunction "VCC_6") (pintype "passive"))
      (node (ref "ICSP") (pin "2") (pinfunction "2_2") (pintype "passive"))
      (node (ref "LCD_1") (pin "2") (pinfunction "2_2") (pintype "passive"))
      (node (ref "MODULES") (pin "12") (pinfunction "12_12") (pintype "passive"))
      (node (ref "MODULES") (pin "14") (pinfunction "14_14") (pintype "passive"))
      (node (ref "R1") (pin "1") (pinfunction "1_1") (pintype "passive"))
      (node (ref "R15") (pin "2") (pinfunction "2_2") (pintype "passive"))
      (node (ref "R16") (pin "2") (pinfunction "2_2") (pintype "passive"))
      (node (ref "R18") (pin "2") (pinfunction "2_2") (pintype "passive"))
      (node (ref "R2") (pin "1") (pinfunction "1_1") (pintype "passive"))
      (node (ref "R20") (pin "1") (pinfunction "1_1") (pintype "passive"))
      (node (ref "R24") (pin "2") (pinfunction "2_2") (pintype "passive"))
      (node (ref "R3") (pin "1") (pinfunction "1_1") (pintype "passive"))
      (node (ref "R4") (pin "1") (pinfunction "1_1") (pintype "passive"))
      (node (ref "R5") (pin "1") (pinfunction "1_1") (pintype "passive"))
      (node (ref "R6") (pin "1") (pinfunction "1_1") (pintype "passive"))
      (node (ref "R8") (pin "2") (pinfunction "2_2") (pintype "passive"))
      (node (ref "R9") (pin "2") (pinfunction "2_2") (pintype "passive"))
      (node (ref "SLIDE") (pin "3") (pinfunction "3_3") (pintype "passive"))
      (node (ref "T1") (pin "3") (pinfunction "E_3") (pintype "passive"))
      (node (ref "VREG") (pin "3") (pinfunction "VO_3") (pintype "passive"))
    )
    (net (code "55") (name "Net-(C19-Pad2)") (class "Default")
      (node (ref "C19") (pin "2") (pinfunction "2_2") (pintype "passive"))
      (node (ref "R22") (pin "2") (pinfunction "2_2") (pintype "passive"))
      (node (ref "R23") (pin "1") (pinfunction "1_1") (pintype "passive"))
    )
    (net (code "56") (name "Net-(C21-Pad1)") (class "Default")
      (node (ref "C21") (pin "1") (pinfunction "1_1") (pintype "passive"))
      (node (ref "DEBUG") (pin "6") (pinfunction "6_6") (pintype "passive"))
    )
    (net (code "57") (name "Net-(D1-PadA)") (class "Default")
      (node (ref "D1") (pin "A") (pinfunction "A_A") (pintype "passive"))
      (node (ref "J1") (pin "GND") (pinfunction "GND_GND") (pintype "bidirectional"))
      (node (ref "J1") (pin "GNDBREAK") (pinfunction "GNDBREAK_GNDBREAK") (pintype "bidirectional"))
    )
    (net (code "58") (name "Net-(IC3-XTAL1)") (class "Default")
      (node (ref "C12") (pin "2") (pinfunction "2_2") (pintype "passive"))
      (node (ref "IC3") (pin "8") (pinfunction "XTAL1_8") (pintype "input"))
      (node (ref "Q1") (pin "1") (pinfunction "1_1") (pintype "passive"))
    )
    (net (code "59") (name "Net-(IC3-XTAL2)") (class "Default")
      (node (ref "C11") (pin "2") (pinfunction "2_2") (pintype "passive"))
      (node (ref "IC3") (pin "7") (pinfunction "XTAL2_7") (pintype "output"))
      (node (ref "Q1") (pin "3") (pinfunction "2_3") (pintype "passive"))
    )
    (net (code "60") (name "Net-(IC5-A)") (class "Default")
      (node (ref "D2") (pin "C") (pinfunction "C_C") (pintype "passive"))
      (node (ref "IC5") (pin "1") (pinfunction "A_1") (pintype "passive"))
      (node (ref "R14") (pin "2") (pinfunction "2_2") (pintype "passive"))
    )
    (net (code "61") (name "Net-(LEDS-Pad1)") (class "Default")
      (node (ref "LEDS") (pin "1") (pinfunction "1_1") (pintype "passive"))
      (node (ref "R10") (pin "2") (pinfunction "2_2") (pintype "passive"))
    )
    (net (code "62") (name "Net-(LEDS-Pad2)") (class "Default")
      (node (ref "LEDS") (pin "2") (pinfunction "2_2") (pintype "passive"))
      (node (ref "R11") (pin "2") (pinfunction "2_2") (pintype "passive"))
    )
    (net (code "63") (name "Net-(LEDS-Pad3)") (class "Default")
      (node (ref "LEDS") (pin "3") (pinfunction "3_3") (pintype "passive"))
      (node (ref "R12") (pin "2") (pinfunction "2_2") (pintype "passive"))
    )
    (net (code "64") (name "Net-(LEDS-Pad4)") (class "Default")
      (node (ref "LEDS") (pin "4") (pinfunction "4_4") (pintype "passive"))
      (node (ref "R13") (pin "2") (pinfunction "2_2") (pintype "passive"))
    )
    (net (code "65") (name "Net-(Q2-B)") (class "Default")
      (node (ref "Q2") (pin "1") (pinfunction "B_1") (pintype "passive"))
      (node (ref "R19") (pin "1") (pinfunction "1_1") (pintype "passive"))
    )
    (net (code "66") (name "Net-(Q2-C)") (class "Default")
      (node (ref "Q2") (pin "3") (pinfunction "C_3") (pintype "passive"))
      (node (ref "R20") (pin "2") (pinfunction "2_2") (pintype "passive"))
      (node (ref "R21") (pin "2") (pinfunction "2_2") (pintype "passive"))
      (node (ref "R22") (pin "1") (pinfunction "1_1") (pintype "passive"))
    )
    (net (code "67") (name "Net-(TUNER-RING)") (class "Default")
      (node (ref "JP1") (pin "3") (pinfunction "3_3") (pintype "passive"))
      (node (ref "TUNER") (pin "R") (pinfunction "RING_R") (pintype "bidirectional"))
    )
    (net (code "68") (name "Net-(TUNER-SHIELD)") (class "Default")
      (node (ref "JP1") (pin "2") (pinfunction "2_2") (pintype "passive"))
      (node (ref "TUNER") (pin "S") (pinfunction "SHIELD_S") (pintype "bidirectional"))
    )
    (net (code "69") (name "Net-(TUNER-TIP)") (class "Default")
      (node (ref "JP1") (pin "1") (pinfunction "1_1") (pintype "passive"))
      (node (ref "TUNER") (pin "T") (pinfunction "TIP_T") (pintype "bidirectional"))
    )
    (net (code "70") (name "Net-(VREG-VI)") (class "Default")
      (node (ref "C7") (pin "+") (pinfunction "+_+") (pintype "passive"))
      (node (ref "C9") (pin "1") (pinfunction "1_1") (pintype "passive"))
      (node (ref "D1") (pin "C") (pinfunction "C_C") (pintype "passive"))
      (node (ref "VREG") (pin "1") (pinfunction "VI_1") (pintype "input"))
    )
    (net (code "71") (name "unconnected-(IC3-(OC1A{slash}PCINT29)PD5-Pad14)") (class "Default")
      (node (ref "IC3") (pin "14") (pinfunction "(OC1A/PCINT29)PD5_14") (pintype "bidirectional"))
    )
    (net (code "72") (name "unconnected-(IC4-P0-Pad4)") (class "Default")
      (node (ref "IC4") (pin "4") (pinfunction "P0_4") (pintype "bidirectional"))
    )
    (net (code "73") (name "unconnected-(IC4-~{INT}-Pad13)") (class "Default")
      (node (ref "IC4") (pin "13") (pinfunction "~{INT}_13") (pintype "output"))
    )
    (net (code "74") (name "unconnected-(INPUT-Pad1)") (class "Default")
      (node (ref "INPUT") (pin "1") (pinfunction "1_1") (pintype "passive"))
    )
    (net (code "75") (name "unconnected-(INPUT-Pad2)") (class "Default")
      (node (ref "INPUT") (pin "2") (pinfunction "2_2") (pintype "passive"))
    )
    (net (code "76") (name "unconnected-(INPUT-Pad3)") (class "Default")
      (node (ref "INPUT") (pin "3") (pinfunction "3_3") (pintype "passive"))
    )
    (net (code "77") (name "unconnected-(OUTPUT-Pad1)") (class "Default")
      (node (ref "OUTPUT") (pin "1") (pinfunction "1_1") (pintype "passive"))
    )
    (net (code "78") (name "unconnected-(OUTPUT-Pad3)") (class "Default")
      (node (ref "OUTPUT") (pin "3") (pinfunction "3_3") (pintype "passive"))
    )
    (net (code "79") (name "unconnected-(TUNER-SW_RING-PadRN)") (class "Default")
      (node (ref "TUNER") (pin "RN") (pinfunction "SW_RING_RN") (pintype "bidirectional"))
    )
    (net (code "80") (name "unconnected-(TUNER-SW_SHLD-PadSN)") (class "Default")
      (node (ref "TUNER") (pin "SN") (pinfunction "SW_SHLD_SN") (pintype "bidirectional"))
    )
    (net (code "81") (name "unconnected-(TUNER-SW_TIP-PadTN)") (class "Default")
      (node (ref "TUNER") (pin "TN") (pinfunction "SW_TIP_TN") (pintype "bidirectional"))
    )
  )
)
